# HeadphoneMixer.net
KiCad netlist of a schematic drawn in EAGLE
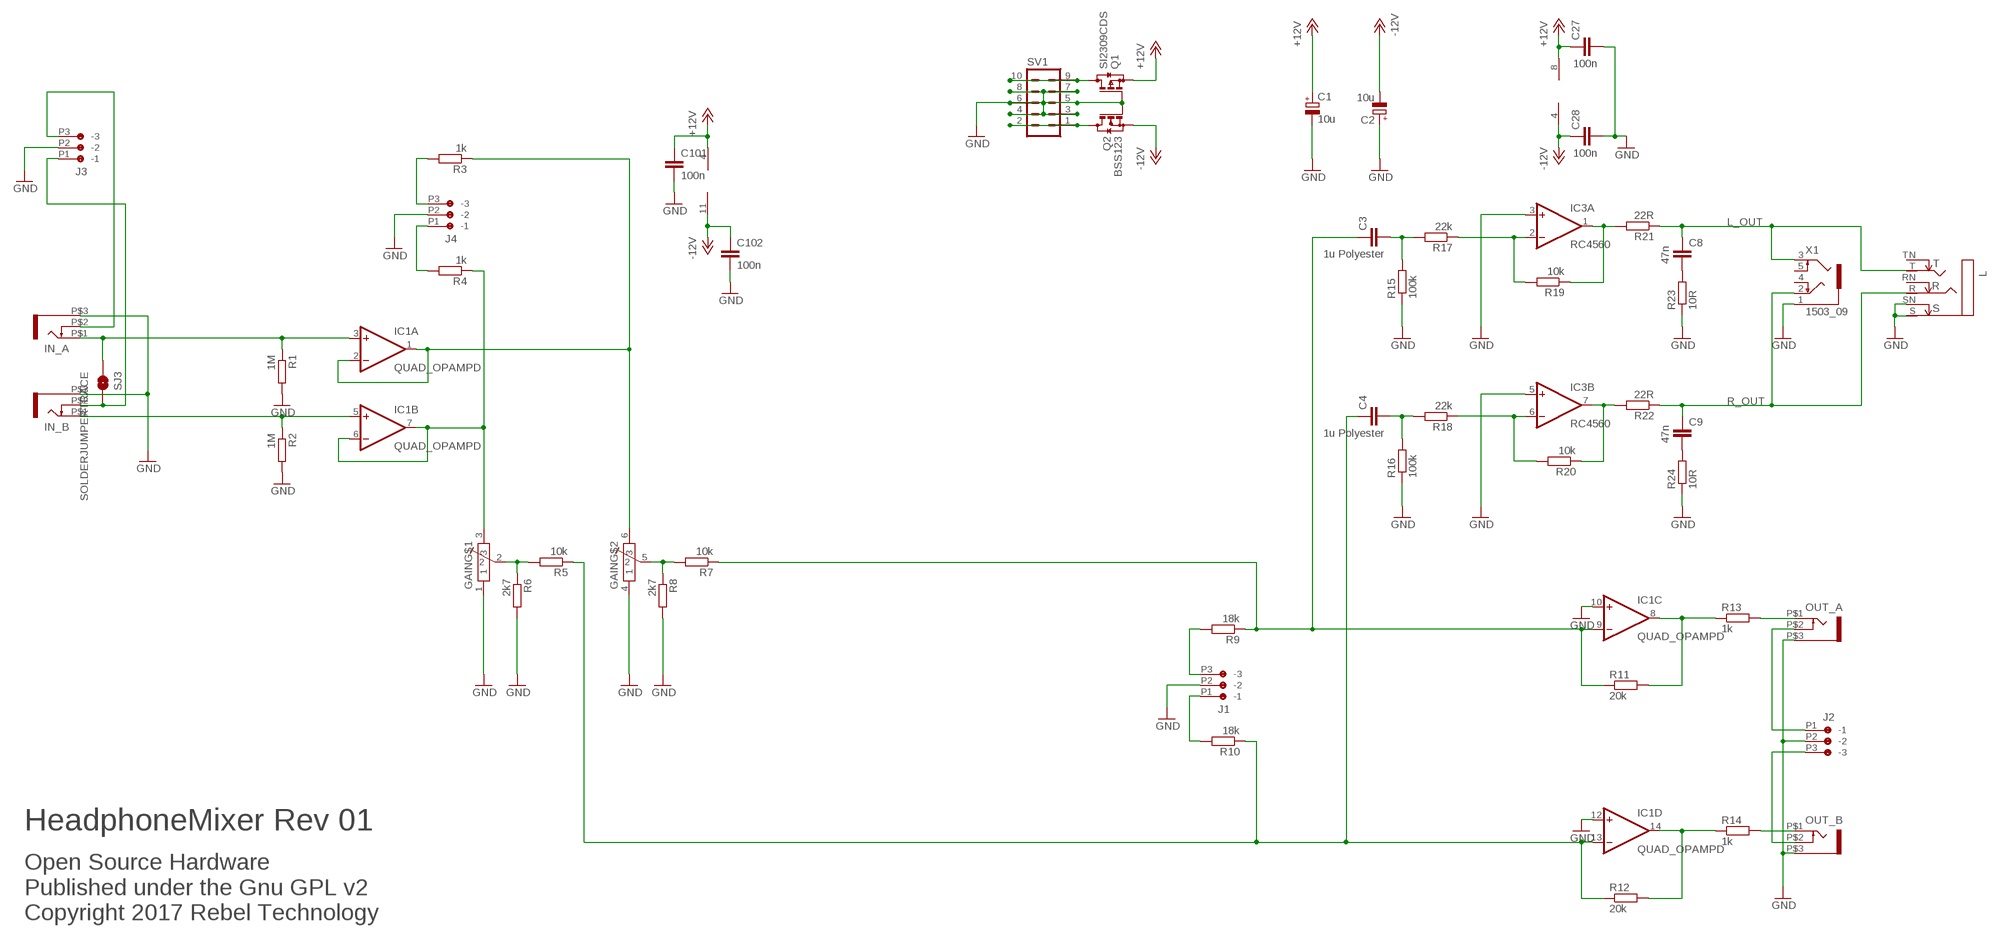
[diagram p0: schematic, sheet 1]

(export (version "E")
  (design (tool "Eeschema 10.0.6"))
  (components
    (comp (ref "C1")
      (value "10u")
      (footprint "eagle-import:153CLV-0505")
      (libsource (lib "eagle-import") (part "CPOL-EU153CLV-0505"))
    )
    (comp (ref "C2")
      (value "10u")
      (footprint "eagle-import:153CLV-0505")
      (libsource (lib "eagle-import") (part "CPOL-EU153CLV-0505"))
    )
    (comp (ref "C3")
      (value "1u Polyester")
      (footprint "eagle-import:C1210")
      (libsource (lib "eagle-import") (part "C-EUC1210"))
    )
    (comp (ref "C4")
      (value "1u Polyester")
      (footprint "eagle-import:C1210")
      (libsource (lib "eagle-import") (part "C-EUC1210"))
    )
    (comp (ref "C8")
      (value "47n")
      (footprint "eagle-import:C0603")
      (libsource (lib "eagle-import") (part "C-EUC0603"))
    )
    (comp (ref "C9")
      (value "47n")
      (footprint "eagle-import:C0603")
      (libsource (lib "eagle-import") (part "C-EUC0603"))
    )
    (comp (ref "C27")
      (value "100n")
      (footprint "eagle-import:C0603")
      (libsource (lib "eagle-import") (part "C-EUC0603"))
    )
    (comp (ref "C28")
      (value "100n")
      (footprint "eagle-import:C0603")
      (libsource (lib "eagle-import") (part "C-EUC0603"))
    )
    (comp (ref "C101")
      (value "100n")
      (footprint "eagle-import:C0603")
      (libsource (lib "eagle-import") (part "C-EUC0603"))
    )
    (comp (ref "C102")
      (value "100n")
      (footprint "eagle-import:C0603")
      (libsource (lib "eagle-import") (part "C-EUC0603"))
    )
    (comp (ref "GAIN")
      (value "POT-BOURNS-PTD902")
      (footprint "eagle-import:POT-BOURNS-PTD902")
      (libsource (lib "eagle-import") (part "POT-BOURNS-PTD902"))
    )
    (comp (ref "IC1")
      (value "QUAD_OPAMPD")
      (footprint "eagle-import:SO14")
      (libsource (lib "eagle-import") (part "QUAD_OPAMPD"))
    )
    (comp (ref "IC3")
      (value "RC4560")
      (footprint "eagle-import:SO08")
      (libsource (lib "eagle-import") (part "NE5532D"))
    )
    (comp (ref "IN_A")
      (value "JACK-UJ-3502-R")
      (footprint "eagle-import:UJ-3502-R")
      (libsource (lib "eagle-import") (part "JACK-UJ-3502-R"))
    )
    (comp (ref "IN_B")
      (value "JACK-UJ-3502-R")
      (footprint "eagle-import:UJ-3502-R")
      (libsource (lib "eagle-import") (part "JACK-UJ-3502-R"))
    )
    (comp (ref "J1")
      (value "CON-JST_PH_3W")
      (footprint "eagle-import:CON-JST_PH_3W")
      (libsource (lib "eagle-import") (part "CON-JST_PH_3W"))
    )
    (comp (ref "J2")
      (value "CON-JST_PH_3W")
      (footprint "eagle-import:CON-JST_PH_3W")
      (libsource (lib "eagle-import") (part "CON-JST_PH_3W"))
    )
    (comp (ref "J3")
      (value "CON-JST_PH_3W")
      (footprint "eagle-import:CON-JST_PH_3W")
      (libsource (lib "eagle-import") (part "CON-JST_PH_3W"))
    )
    (comp (ref "J4")
      (value "CON-JST_PH_3W")
      (footprint "eagle-import:CON-JST_PH_3W")
      (libsource (lib "eagle-import") (part "CON-JST_PH_3W"))
    )
    (comp (ref "L")
      (value "NEUTRIK_NMJ6HCD2")
      (footprint "eagle-import:NMJ6HCD2")
      (libsource (lib "eagle-import") (part "NEUTRIK_NMJ6HCD2"))
    )
    (comp (ref "OUT_A")
      (value "JACK-UJ-3502-R")
      (footprint "eagle-import:UJ-3502-R")
      (libsource (lib "eagle-import") (part "JACK-UJ-3502-R"))
    )
    (comp (ref "OUT_B")
      (value "JACK-UJ-3502-R")
      (footprint "eagle-import:UJ-3502-R")
      (libsource (lib "eagle-import") (part "JACK-UJ-3502-R"))
    )
    (comp (ref "Q1")
      (value "SI2309CDS")
      (footprint "eagle-import:SOT23")
      (libsource (lib "eagle-import") (part "BSS84"))
    )
    (comp (ref "Q2")
      (value "BSS123")
      (footprint "eagle-import:SOT23")
      (libsource (lib "eagle-import") (part "BSS123"))
    )
    (comp (ref "R1")
      (value "1M")
      (footprint "eagle-import:0603")
      (libsource (lib "eagle-import") (part "R-EU_0603"))
    )
    (comp (ref "R2")
      (value "1M")
      (footprint "eagle-import:0603")
      (libsource (lib "eagle-import") (part "R-EU_0603"))
    )
    (comp (ref "R3")
      (value "1k")
      (footprint "eagle-import:0603")
      (libsource (lib "eagle-import") (part "R-EU_0603"))
    )
    (comp (ref "R4")
      (value "1k")
      (footprint "eagle-import:0603")
      (libsource (lib "eagle-import") (part "R-EU_0603"))
    )
    (comp (ref "R5")
      (value "10k")
      (footprint "eagle-import:0603")
      (libsource (lib "eagle-import") (part "R-EU_0603"))
    )
    (comp (ref "R6")
      (value "2k7")
      (footprint "eagle-import:0603")
      (libsource (lib "eagle-import") (part "R-EU_0603"))
    )
    (comp (ref "R7")
      (value "10k")
      (footprint "eagle-import:0603")
      (libsource (lib "eagle-import") (part "R-EU_0603"))
    )
    (comp (ref "R8")
      (value "2k7")
      (footprint "eagle-import:0603")
      (libsource (lib "eagle-import") (part "R-EU_0603"))
    )
    (comp (ref "R9")
      (value "18k")
      (footprint "eagle-import:0603")
      (libsource (lib "eagle-import") (part "R-EU_0603"))
    )
    (comp (ref "R10")
      (value "18k")
      (footprint "eagle-import:0603")
      (libsource (lib "eagle-import") (part "R-EU_0603"))
    )
    (comp (ref "R11")
      (value "20k")
      (footprint "eagle-import:0603")
      (libsource (lib "eagle-import") (part "R-EU_0603"))
    )
    (comp (ref "R12")
      (value "20k")
      (footprint "eagle-import:0603")
      (libsource (lib "eagle-import") (part "R-EU_0603"))
    )
    (comp (ref "R13")
      (value "1k")
      (footprint "eagle-import:0603")
      (libsource (lib "eagle-import") (part "R-EU_0603"))
    )
    (comp (ref "R14")
      (value "1k")
      (footprint "eagle-import:0603")
      (libsource (lib "eagle-import") (part "R-EU_0603"))
    )
    (comp (ref "R15")
      (value "100k")
      (footprint "eagle-import:0603")
      (libsource (lib "eagle-import") (part "R-EU_0603"))
    )
    (comp (ref "R16")
      (value "100k")
      (footprint "eagle-import:0603")
      (libsource (lib "eagle-import") (part "R-EU_0603"))
    )
    (comp (ref "R17")
      (value "22k")
      (footprint "eagle-import:0603")
      (libsource (lib "eagle-import") (part "R-EU_0603"))
    )
    (comp (ref "R18")
      (value "22k")
      (footprint "eagle-import:0603")
      (libsource (lib "eagle-import") (part "R-EU_0603"))
    )
    (comp (ref "R19")
      (value "10k")
      (footprint "eagle-import:0603")
      (libsource (lib "eagle-import") (part "R-EU_0603"))
    )
    (comp (ref "R20")
      (value "10k")
      (footprint "eagle-import:0603")
      (libsource (lib "eagle-import") (part "R-EU_0603"))
    )
    (comp (ref "R21")
      (value "22R")
      (footprint "eagle-import:0603")
      (libsource (lib "eagle-import") (part "R-EU_0603"))
    )
    (comp (ref "R22")
      (value "22R")
      (footprint "eagle-import:0603")
      (libsource (lib "eagle-import") (part "R-EU_0603"))
    )
    (comp (ref "R23")
      (value "10R")
      (footprint "eagle-import:0603")
      (libsource (lib "eagle-import") (part "R-EU_0603"))
    )
    (comp (ref "R24")
      (value "10R")
      (footprint "eagle-import:0603")
      (libsource (lib "eagle-import") (part "R-EU_0603"))
    )
    (comp (ref "SJ3")
      (value "SOLDERJUMPERTRACE")
      (footprint "eagle-import:SJ_2S-TRACE")
      (libsource (lib "eagle-import") (part "SOLDERJUMPERTRACE"))
    )
    (comp (ref "SV1")
      (value "MA05-2")
      (footprint "eagle-import:MA05-2")
      (libsource (lib "eagle-import") (part "MA05-2"))
    )
    (comp (ref "X1")
      (value "1503_09")
      (footprint "eagle-import:1503_09")
      (libsource (lib "eagle-import") (part "1503_09"))
    )
  )
  (nets
    (net (code "1") (name "+12V") (class "Default")
      (node (ref "C1") (pin "+") (pinfunction "+_+") (pintype "passive"))
      (node (ref "C101") (pin "1") (pinfunction "1_1") (pintype "passive"))
      (node (ref "C27") (pin "1") (pinfunction "1_1") (pintype "passive"))
      (node (ref "IC1") (pin "4") (pinfunction "V+_4") (pintype "power_in"))
      (node (ref "IC3") (pin "8") (pinfunction "V+_8") (pintype "power_in"))
      (node (ref "Q1") (pin "2") (pinfunction "S_2") (pintype "passive"))
    )
    (net (code "2") (name "-12V") (class "Default")
      (node (ref "C102") (pin "1") (pinfunction "1_1") (pintype "passive"))
      (node (ref "C2") (pin "-") (pinfunction "-_-") (pintype "passive"))
      (node (ref "C28") (pin "1") (pinfunction "1_1") (pintype "passive"))
      (node (ref "IC1") (pin "11") (pinfunction "V-_11") (pintype "power_in"))
      (node (ref "IC3") (pin "4") (pinfunction "V-_4") (pintype "power_in"))
      (node (ref "Q2") (pin "2") (pinfunction "S_2") (pintype "passive"))
    )
    (net (code "3") (name "/L_OUT") (class "Default")
      (node (ref "C8") (pin "1") (pinfunction "1_1") (pintype "passive"))
      (node (ref "L") (pin "T") (pinfunction "T_T") (pintype "passive"))
      (node (ref "R21") (pin "1") (pinfunction "1_1") (pintype "passive"))
      (node (ref "X1") (pin "3") (pinfunction "3_3") (pintype "passive"))
    )
    (net (code "4") (name "/R_OUT") (class "Default")
      (node (ref "C9") (pin "1") (pinfunction "1_1") (pintype "passive"))
      (node (ref "L") (pin "R") (pinfunction "R_R") (pintype "passive"))
      (node (ref "R22") (pin "1") (pinfunction "1_1") (pintype "passive"))
      (node (ref "X1") (pin "2") (pinfunction "2_2") (pintype "passive"))
    )
    (net (code "5") (name "GND") (class "Default")
      (node (ref "C1") (pin "-") (pinfunction "-_-") (pintype "passive"))
      (node (ref "C101") (pin "2") (pinfunction "2_2") (pintype "passive"))
      (node (ref "C102") (pin "2") (pinfunction "2_2") (pintype "passive"))
      (node (ref "C2") (pin "+") (pinfunction "+_+") (pintype "passive"))
      (node (ref "C27") (pin "2") (pinfunction "2_2") (pintype "passive"))
      (node (ref "C28") (pin "2") (pinfunction "2_2") (pintype "passive"))
      (node (ref "GAIN") (pin "1") (pinfunction "1_1") (pintype "bidirectional"))
      (node (ref "GAIN") (pin "4") (pinfunction "1_4") (pintype "bidirectional"))
      (node (ref "IC1") (pin "10") (pinfunction "+IN_10") (pintype "input"))
      (node (ref "IC1") (pin "12") (pinfunction "+IN_12") (pintype "input"))
      (node (ref "IC3") (pin "3") (pinfunction "+IN_3") (pintype "input"))
      (node (ref "IC3") (pin "5") (pinfunction "+IN_5") (pintype "input"))
      (node (ref "IN_A") (pin "P$3") (pinfunction "SLEEVE_P$3") (pintype "passive"))
      (node (ref "IN_B") (pin "P$3") (pinfunction "SLEEVE_P$3") (pintype "passive"))
      (node (ref "J1") (pin "P2") (pinfunction "-2_P2") (pintype "bidirectional"))
      (node (ref "J2") (pin "P2") (pinfunction "-2_P2") (pintype "bidirectional"))
      (node (ref "J3") (pin "P2") (pinfunction "-2_P2") (pintype "bidirectional"))
      (node (ref "J4") (pin "P2") (pinfunction "-2_P2") (pintype "bidirectional"))
      (node (ref "L") (pin "S") (pinfunction "S_S") (pintype "passive"))
      (node (ref "L") (pin "SN") (pinfunction "SN_SN") (pintype "passive"))
      (node (ref "OUT_A") (pin "P$3") (pinfunction "SLEEVE_P$3") (pintype "passive"))
      (node (ref "OUT_B") (pin "P$3") (pinfunction "SLEEVE_P$3") (pintype "passive"))
      (node (ref "Q1") (pin "1") (pinfunction "G_1") (pintype "passive"))
      (node (ref "Q2") (pin "1") (pinfunction "G_1") (pintype "passive"))
      (node (ref "R1") (pin "2") (pinfunction "2_2") (pintype "passive"))
      (node (ref "R15") (pin "1") (pinfunction "1_1") (pintype "passive"))
      (node (ref "R16") (pin "1") (pinfunction "1_1") (pintype "passive"))
      (node (ref "R2") (pin "2") (pinfunction "2_2") (pintype "passive"))
      (node (ref "R23") (pin "1") (pinfunction "1_1") (pintype "passive"))
      (node (ref "R24") (pin "1") (pinfunction "1_1") (pintype "passive"))
      (node (ref "R6") (pin "2") (pinfunction "2_2") (pintype "passive"))
      (node (ref "R8") (pin "2") (pinfunction "2_2") (pintype "passive"))
      (node (ref "SV1") (pin "3") (pinfunction "3_3") (pintype "passive"))
      (node (ref "SV1") (pin "4") (pinfunction "4_4") (pintype "passive"))
      (node (ref "SV1") (pin "5") (pinfunction "5_5") (pintype "passive"))
      (node (ref "SV1") (pin "6") (pinfunction "6_6") (pintype "passive"))
      (node (ref "SV1") (pin "7") (pinfunction "7_7") (pintype "passive"))
      (node (ref "SV1") (pin "8") (pinfunction "8_8") (pintype "passive"))
      (node (ref "X1") (pin "1") (pinfunction "1_1") (pintype "passive"))
    )
    (net (code "6") (name "Net-(C3-Pad2)") (class "Default")
      (node (ref "C3") (pin "2") (pinfunction "2_2") (pintype "passive"))
      (node (ref "R15") (pin "2") (pinfunction "2_2") (pintype "passive"))
      (node (ref "R17") (pin "2") (pinfunction "2_2") (pintype "passive"))
    )
    (net (code "7") (name "Net-(C4-Pad2)") (class "Default")
      (node (ref "C4") (pin "2") (pinfunction "2_2") (pintype "passive"))
      (node (ref "R16") (pin "2") (pinfunction "2_2") (pintype "passive"))
      (node (ref "R18") (pin "2") (pinfunction "2_2") (pintype "passive"))
    )
    (net (code "8") (name "Net-(C8-Pad2)") (class "Default")
      (node (ref "C8") (pin "2") (pinfunction "2_2") (pintype "passive"))
      (node (ref "R23") (pin "2") (pinfunction "2_2") (pintype "passive"))
    )
    (net (code "9") (name "Net-(C9-Pad2)") (class "Default")
      (node (ref "C9") (pin "2") (pinfunction "2_2") (pintype "passive"))
      (node (ref "R24") (pin "2") (pinfunction "2_2") (pintype "passive"))
    )
    (net (code "10") (name "Net-(GAIN-Pad2)") (class "Default")
      (node (ref "GAIN") (pin "2") (pinfunction "2_2") (pintype "bidirectional"))
      (node (ref "R5") (pin "2") (pinfunction "2_2") (pintype "passive"))
      (node (ref "R6") (pin "1") (pinfunction "1_1") (pintype "passive"))
    )
    (net (code "11") (name "Net-(GAINB-2)") (class "Default")
      (node (ref "GAIN") (pin "5") (pinfunction "2_5") (pintype "bidirectional"))
      (node (ref "R7") (pin "2") (pinfunction "2_2") (pintype "passive"))
      (node (ref "R8") (pin "1") (pinfunction "1_1") (pintype "passive"))
    )
    (net (code "12") (name "Net-(GAINB-3)") (class "Default")
      (node (ref "GAIN") (pin "6") (pinfunction "3_6") (pintype "bidirectional"))
      (node (ref "IC1") (pin "1") (pinfunction "OUT_1") (pintype "output"))
      (node (ref "IC1") (pin "2") (pinfunction "-IN_2") (pintype "input"))
      (node (ref "R3") (pin "1") (pinfunction "1_1") (pintype "passive"))
    )
    (net (code "13") (name "Net-(IC1A-+IN)") (class "Default")
      (node (ref "IC1") (pin "3") (pinfunction "+IN_3") (pintype "input"))
      (node (ref "IN_A") (pin "P$1") (pinfunction "TIP_P$1") (pintype "passive"))
      (node (ref "R1") (pin "1") (pinfunction "1_1") (pintype "passive"))
      (node (ref "SJ3") (pin "1") (pinfunction "1_1") (pintype "passive"))
    )
    (net (code "14") (name "Net-(IC1B-+IN)") (class "Default")
      (node (ref "IC1") (pin "5") (pinfunction "+IN_5") (pintype "input"))
      (node (ref "IN_B") (pin "P$1") (pinfunction "TIP_P$1") (pintype "passive"))
      (node (ref "R2") (pin "1") (pinfunction "1_1") (pintype "passive"))
    )
    (net (code "15") (name "Net-(IC1B--IN)") (class "Default")
      (node (ref "GAIN") (pin "3") (pinfunction "3_3") (pintype "bidirectional"))
      (node (ref "IC1") (pin "6") (pinfunction "-IN_6") (pintype "input"))
      (node (ref "IC1") (pin "7") (pinfunction "OUT_7") (pintype "output"))
      (node (ref "R4") (pin "1") (pinfunction "1_1") (pintype "passive"))
    )
    (net (code "16") (name "Net-(IC1C--IN)") (class "Default")
      (node (ref "C3") (pin "1") (pinfunction "1_1") (pintype "passive"))
      (node (ref "IC1") (pin "9") (pinfunction "-IN_9") (pintype "input"))
      (node (ref "R11") (pin "1") (pinfunction "1_1") (pintype "passive"))
      (node (ref "R7") (pin "1") (pinfunction "1_1") (pintype "passive"))
      (node (ref "R9") (pin "1") (pinfunction "1_1") (pintype "passive"))
    )
    (net (code "17") (name "Net-(IC1C-OUT)") (class "Default")
      (node (ref "IC1") (pin "8") (pinfunction "OUT_8") (pintype "output"))
      (node (ref "R11") (pin "2") (pinfunction "2_2") (pintype "passive"))
      (node (ref "R13") (pin "1") (pinfunction "1_1") (pintype "passive"))
    )
    (net (code "18") (name "Net-(IC1D--IN)") (class "Default")
      (node (ref "C4") (pin "1") (pinfunction "1_1") (pintype "passive"))
      (node (ref "IC1") (pin "13") (pinfunction "-IN_13") (pintype "input"))
      (node (ref "R10") (pin "1") (pinfunction "1_1") (pintype "passive"))
      (node (ref "R12") (pin "1") (pinfunction "1_1") (pintype "passive"))
      (node (ref "R5") (pin "1") (pinfunction "1_1") (pintype "passive"))
    )
    (net (code "19") (name "Net-(IC1D-OUT)") (class "Default")
      (node (ref "IC1") (pin "14") (pinfunction "OUT_14") (pintype "output"))
      (node (ref "R12") (pin "2") (pinfunction "2_2") (pintype "passive"))
      (node (ref "R14") (pin "1") (pinfunction "1_1") (pintype "passive"))
    )
    (net (code "20") (name "Net-(IC3A--IN)") (class "Default")
      (node (ref "IC3") (pin "2") (pinfunction "-IN_2") (pintype "input"))
      (node (ref "R17") (pin "1") (pinfunction "1_1") (pintype "passive"))
      (node (ref "R19") (pin "2") (pinfunction "2_2") (pintype "passive"))
    )
    (net (code "21") (name "Net-(IC3A-OUT)") (class "Default")
      (node (ref "IC3") (pin "1") (pinfunction "OUT_1") (pintype "output"))
      (node (ref "R19") (pin "1") (pinfunction "1_1") (pintype "passive"))
      (node (ref "R21") (pin "2") (pinfunction "2_2") (pintype "passive"))
    )
    (net (code "22") (name "Net-(IC3B--IN)") (class "Default")
      (node (ref "IC3") (pin "6") (pinfunction "-IN_6") (pintype "input"))
      (node (ref "R18") (pin "1") (pinfunction "1_1") (pintype "passive"))
      (node (ref "R20") (pin "2") (pinfunction "2_2") (pintype "passive"))
    )
    (net (code "23") (name "Net-(IC3B-OUT)") (class "Default")
      (node (ref "IC3") (pin "7") (pinfunction "OUT_7") (pintype "output"))
      (node (ref "R20") (pin "1") (pinfunction "1_1") (pintype "passive"))
      (node (ref "R22") (pin "2") (pinfunction "2_2") (pintype "passive"))
    )
    (net (code "24") (name "Net-(IN_A-SW)") (class "Default")
      (node (ref "IN_A") (pin "P$2") (pinfunction "SW_P$2") (pintype "passive"))
      (node (ref "J3") (pin "P3") (pinfunction "-3_P3") (pintype "bidirectional"))
    )
    (net (code "25") (name "Net-(IN_B-SW)") (class "Default")
      (node (ref "IN_B") (pin "P$2") (pinfunction "SW_P$2") (pintype "passive"))
      (node (ref "J3") (pin "P1") (pinfunction "-1_P1") (pintype "bidirectional"))
      (node (ref "SJ3") (pin "2") (pinfunction "2_2") (pintype "passive"))
    )
    (net (code "26") (name "Net-(J1--1)") (class "Default")
      (node (ref "J1") (pin "P1") (pinfunction "-1_P1") (pintype "bidirectional"))
      (node (ref "R10") (pin "2") (pinfunction "2_2") (pintype "passive"))
    )
    (net (code "27") (name "Net-(J1--3)") (class "Default")
      (node (ref "J1") (pin "P3") (pinfunction "-3_P3") (pintype "bidirectional"))
      (node (ref "R9") (pin "2") (pinfunction "2_2") (pintype "passive"))
    )
    (net (code "28") (name "Net-(J2--1)") (class "Default")
      (node (ref "J2") (pin "P1") (pinfunction "-1_P1") (pintype "bidirectional"))
      (node (ref "OUT_A") (pin "P$2") (pinfunction "SW_P$2") (pintype "passive"))
    )
    (net (code "29") (name "Net-(J2--3)") (class "Default")
      (node (ref "J2") (pin "P3") (pinfunction "-3_P3") (pintype "bidirectional"))
      (node (ref "OUT_B") (pin "P$2") (pinfunction "SW_P$2") (pintype "passive"))
    )
    (net (code "30") (name "Net-(J4--1)") (class "Default")
      (node (ref "J4") (pin "P1") (pinfunction "-1_P1") (pintype "bidirectional"))
      (node (ref "R4") (pin "2") (pinfunction "2_2") (pintype "passive"))
    )
    (net (code "31") (name "Net-(J4--3)") (class "Default")
      (node (ref "J4") (pin "P3") (pinfunction "-3_P3") (pintype "bidirectional"))
      (node (ref "R3") (pin "2") (pinfunction "2_2") (pintype "passive"))
    )
    (net (code "32") (name "Net-(OUT_A-TIP)") (class "Default")
      (node (ref "OUT_A") (pin "P$1") (pinfunction "TIP_P$1") (pintype "passive"))
      (node (ref "R13") (pin "2") (pinfunction "2_2") (pintype "passive"))
    )
    (net (code "33") (name "Net-(OUT_B-TIP)") (class "Default")
      (node (ref "OUT_B") (pin "P$1") (pinfunction "TIP_P$1") (pintype "passive"))
      (node (ref "R14") (pin "2") (pinfunction "2_2") (pintype "passive"))
    )
    (net (code "34") (name "Net-(Q1-D)") (class "Default")
      (node (ref "Q1") (pin "3") (pinfunction "D_3") (pintype "passive"))
      (node (ref "SV1") (pin "10") (pinfunction "10_10") (pintype "passive"))
      (node (ref "SV1") (pin "9") (pinfunction "9_9") (pintype "passive"))
    )
    (net (code "35") (name "Net-(Q2-D)") (class "Default")
      (node (ref "Q2") (pin "3") (pinfunction "D_3") (pintype "passive"))
      (node (ref "SV1") (pin "1") (pinfunction "1_1") (pintype "passive"))
      (node (ref "SV1") (pin "2") (pinfunction "2_2") (pintype "passive"))
    )
    (net (code "36") (name "unconnected-(L-PadRN)") (class "Default")
      (node (ref "L") (pin "RN") (pinfunction "RN_RN") (pintype "passive"))
    )
    (net (code "37") (name "unconnected-(L-PadTN)") (class "Default")
      (node (ref "L") (pin "TN") (pinfunction "TN_TN") (pintype "passive"))
    )
    (net (code "38") (name "unconnected-(X1-Pad4)") (class "Default")
      (node (ref "X1") (pin "4") (pinfunction "4_4") (pintype "passive"))
    )
    (net (code "39") (name "unconnected-(X1-Pad5)") (class "Default")
      (node (ref "X1") (pin "5") (pinfunction "5_5") (pintype "passive"))
    )
  )
)
